# GPU_USB_PWM_Fan_Controller.net
KiCad netlist of a schematic drawn in EasyEDA Pro
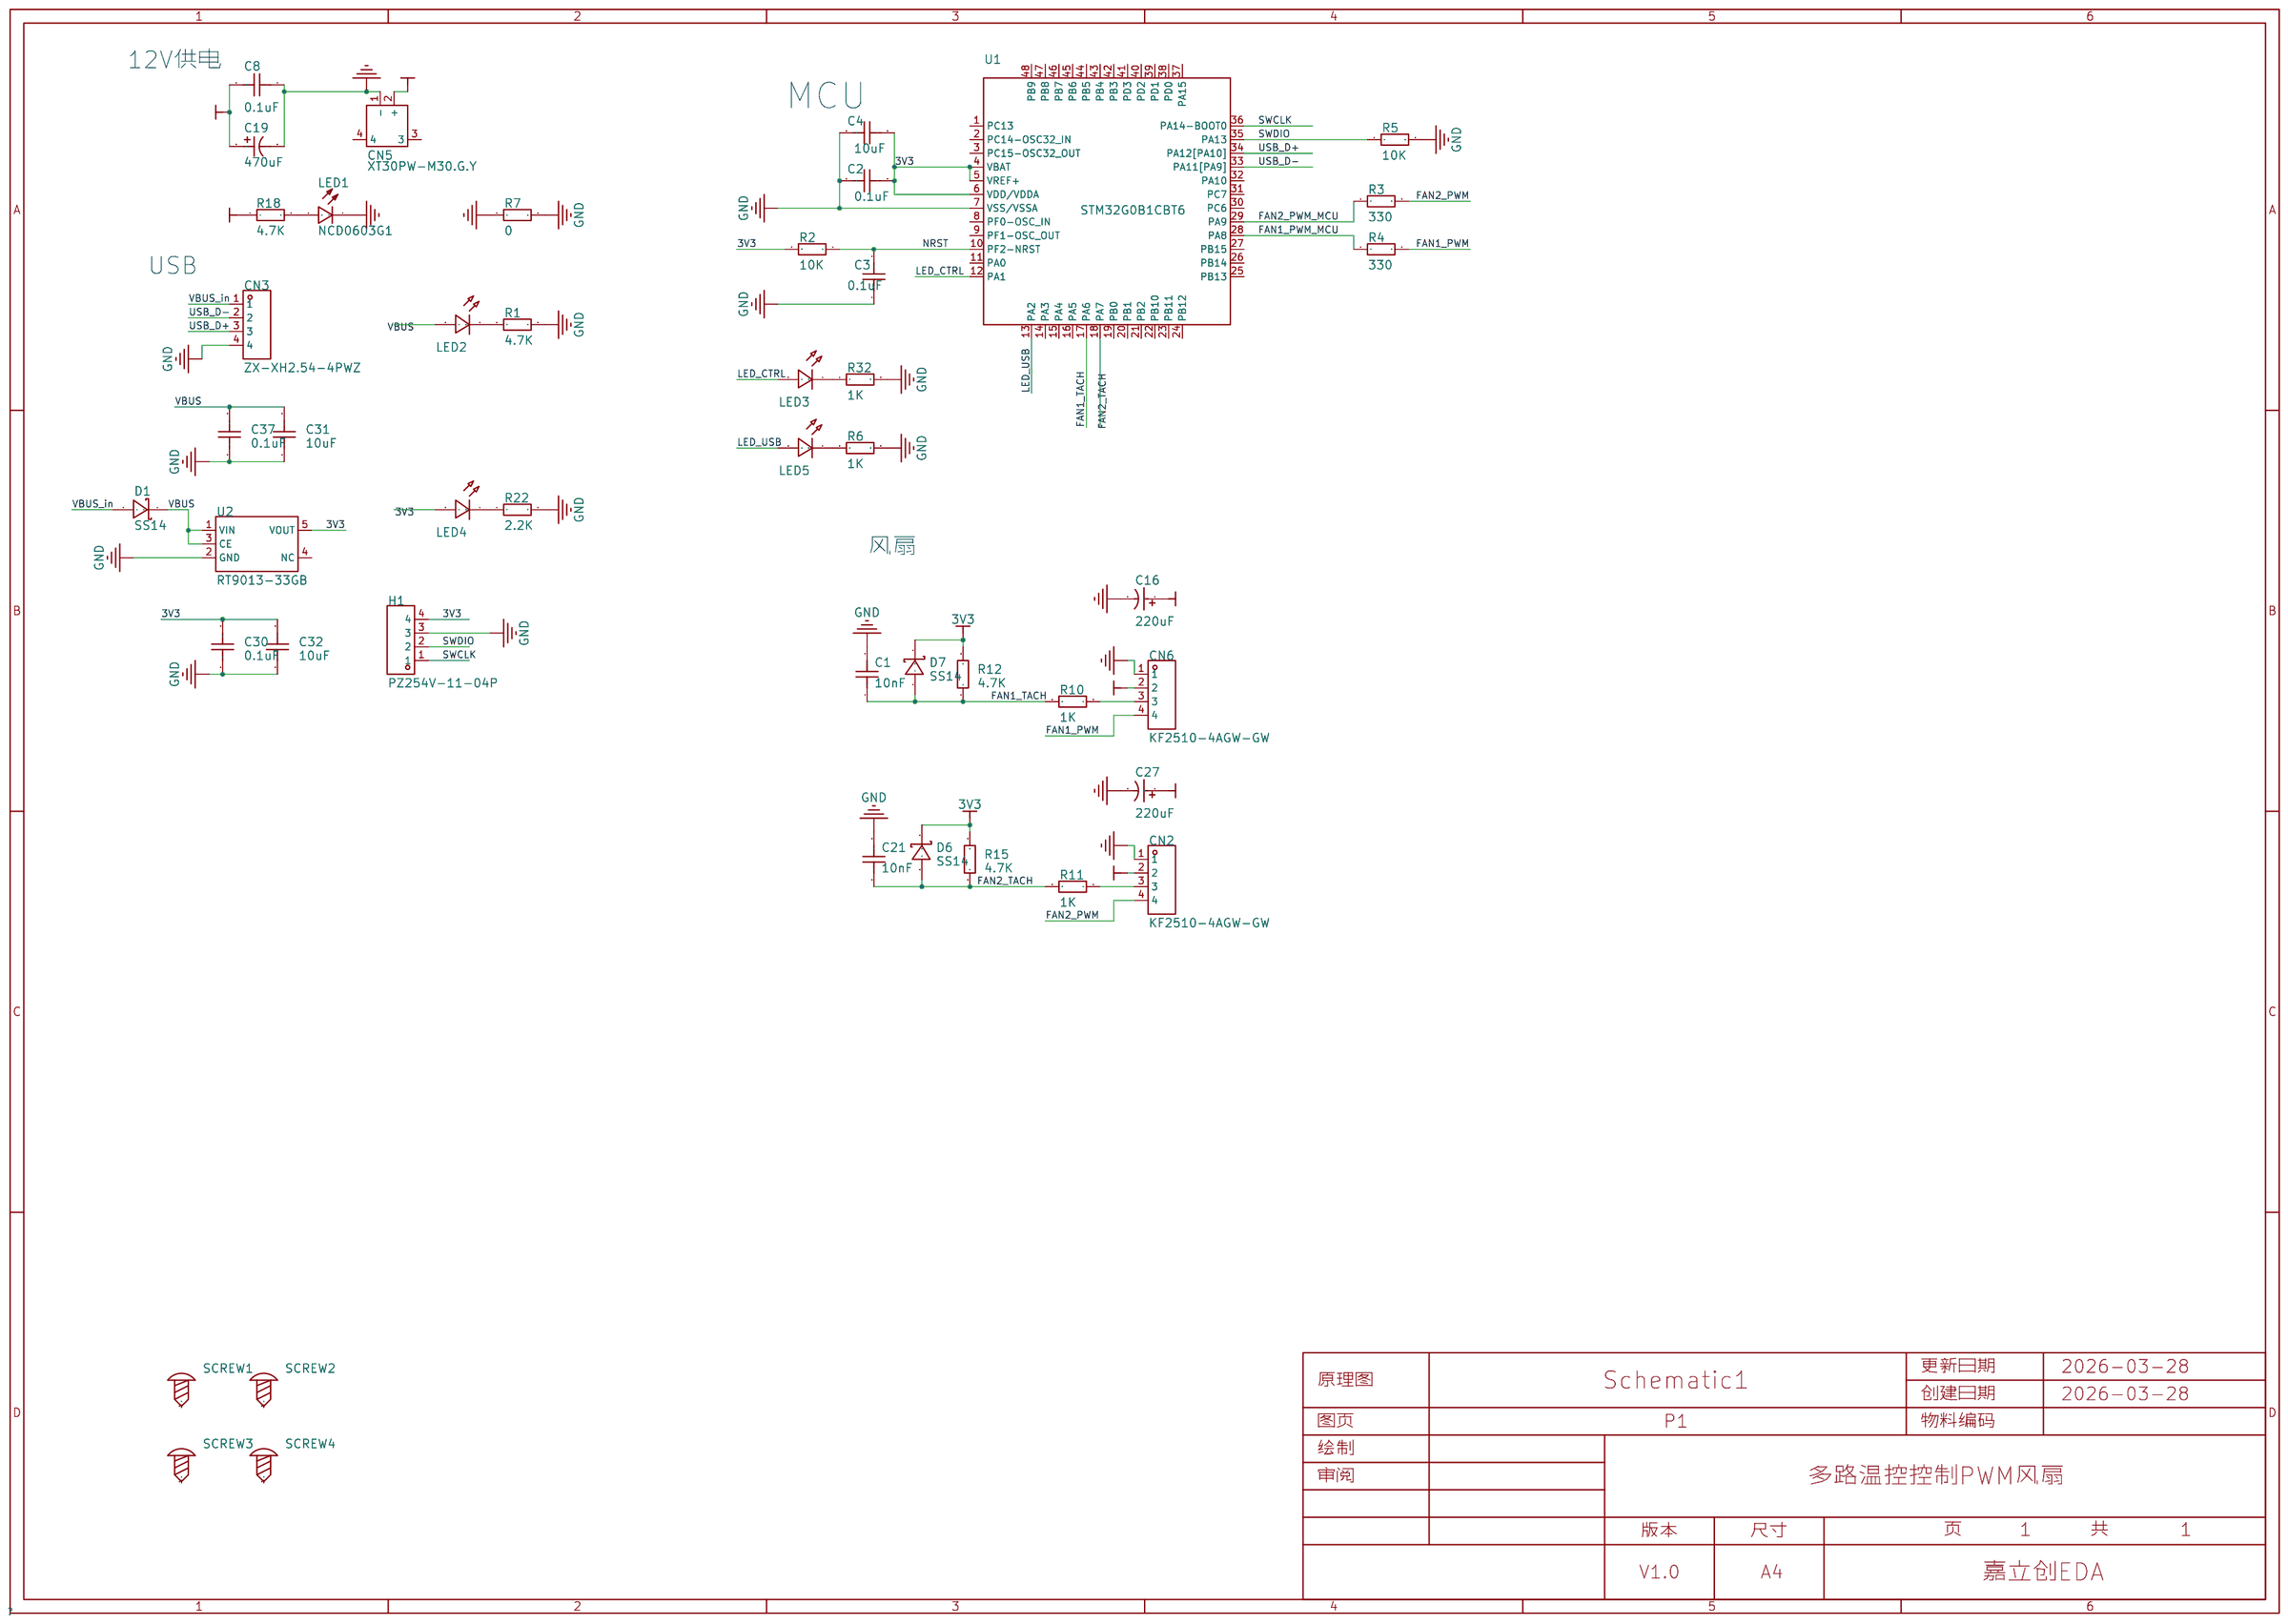
[diagram p0: schematic sheet]

(export (version "E")
  (design (tool "Eeschema 10.0.6"))
  (components
    (comp (ref "C1")
      (value "10nF")
      (footprint "easyedapro:C0603")
      (libsource (lib "easyedapro") (part "Capacitance"))
    )
    (comp (ref "C2")
      (value "0.1uF")
      (footprint "easyedapro:C0603")
      (libsource (lib "easyedapro") (part "Capacitance"))
    )
    (comp (ref "C3")
      (value "0.1uF")
      (footprint "easyedapro:C0603")
      (libsource (lib "easyedapro") (part "Capacitance"))
    )
    (comp (ref "C4")
      (value "10uF")
      (footprint "easyedapro:C0603")
      (libsource (lib "easyedapro") (part "Capacitance"))
    )
    (comp (ref "C8")
      (value "0.1uF")
      (footprint "easyedapro:C0603")
      (libsource (lib "easyedapro") (part "Capacitance"))
    )
    (comp (ref "C16")
      (value "220uF")
      (footprint "easyedapro:CAP-SMD_BD6.3-L6.6-W6.6-FD")
      (fields (field (name "Manufacturer Part") "RVT1A221M0605") (field (name "Manufacturer") "ROQANG(容强)"))
      (libsource (lib "easyedapro") (part "RVT1A221M0605-C72494"))
    )
    (comp (ref "C19")
      (value "470uF")
      (footprint "easyedapro:CAP-SMD_BD6.3-L6.6-W6.6-LS7.6-FD")
      (fields
        (field (name "Manufacturer Part") "RVT470UF10V67RV0159")
        (field (name "Manufacturer") "KNSCHA(科尼盛)")
      )
      (libsource (lib "easyedapro") (part "RVT470UF10V67RV0159"))
    )
    (comp (ref "C21")
      (value "10nF")
      (footprint "easyedapro:C0603")
      (libsource (lib "easyedapro") (part "Capacitance"))
    )
    (comp (ref "C27")
      (value "220uF")
      (footprint "easyedapro:CAP-SMD_BD6.3-L6.6-W6.6-FD")
      (fields (field (name "Manufacturer Part") "RVT1A221M0605") (field (name "Manufacturer") "ROQANG(容强)"))
      (libsource (lib "easyedapro") (part "RVT1A221M0605-C72494"))
    )
    (comp (ref "C30")
      (value "0.1uF")
      (footprint "easyedapro:C0603")
      (libsource (lib "easyedapro") (part "Capacitance"))
    )
    (comp (ref "C31")
      (value "10uF")
      (footprint "easyedapro:C0603")
      (libsource (lib "easyedapro") (part "Capacitance"))
    )
    (comp (ref "C32")
      (value "10uF")
      (footprint "easyedapro:C0603")
      (libsource (lib "easyedapro") (part "Capacitance"))
    )
    (comp (ref "C37")
      (value "0.1uF")
      (footprint "easyedapro:C0603")
      (libsource (lib "easyedapro") (part "Capacitance"))
    )
    (comp (ref "CN2")
      (value "KF2510-4AGW-GW")
      (footprint "easyedapro:CONN-TH_4P-P2.54_CAX_KF2510-4AGW-GW")
      (description "插针结构:1x4P;间距:2.54mm;安装方式:弯插;参考系列:-;总PIN数:4P;排数:1;每排PIN数:4;行距:-;额定电流:3A;触头材质:黄铜;工作温度:-25℃~+85℃;")
      (fields (field (name "Manufacturer") "CAX(创都)"))
      (libsource (lib "easyedapro") (part "KF2510-4AGW-GW"))
    )
    (comp (ref "CN3")
      (value "ZX-XH2.54-4PWZ")
      (footprint "easyedapro:CONN-TH_4P-P2.50_ZX-XH2.54-4PWZ")
      (fields (field (name "Manufacturer") "Megastar(兆星)"))
      (libsource (lib "easyedapro") (part "ZX-XH2.54-4PWZ"))
    )
    (comp (ref "CN5")
      (value "XT30PW-M30.G.Y")
      (footprint "easyedapro:CONN-TH_XT30PW-M")
      (fields (field (name "Manufacturer") "AMASS(艾迈斯)"))
      (libsource (lib "easyedapro") (part "XT30PW-M"))
    )
    (comp (ref "CN6")
      (value "KF2510-4AGW-GW")
      (footprint "easyedapro:CONN-TH_4P-P2.54_CAX_KF2510-4AGW-GW")
      (description "插针结构:1x4P;间距:2.54mm;安装方式:弯插;参考系列:-;总PIN数:4P;排数:1;每排PIN数:4;行距:-;额定电流:3A;触头材质:黄铜;工作温度:-25℃~+85℃;")
      (fields (field (name "Manufacturer") "CAX(创都)"))
      (libsource (lib "easyedapro") (part "KF2510-4AGW-GW"))
    )
    (comp (ref "D1")
      (value "SS14")
      (footprint "easyedapro:SMA_L4.3-W2.6-LS5.2-RD")
      (description "正向压降(Vf):500mV@1A;直流反向耐压(Vr):40V;整流电流:1A;")
      (fields (field (name "Manufacturer") "onsemi(安森美)"))
      (libsource (lib "easyedapro") (part "SS14_C83852"))
    )
    (comp (ref "D6")
      (value "SS14")
      (footprint "easyedapro:SMA_L4.3-W2.6-LS5.2-RD")
      (fields (field (name "Manufacturer") "onsemi(安森美)"))
      (libsource (lib "easyedapro") (part "SS14_C83852"))
    )
    (comp (ref "D7")
      (value "SS14")
      (footprint "easyedapro:SMA_L4.3-W2.6-LS5.2-RD")
      (fields (field (name "Manufacturer") "onsemi(安森美)"))
      (libsource (lib "easyedapro") (part "SS14_C83852"))
    )
    (comp (ref "H1")
      (value "PZ254V-11-04P")
      (footprint "easyedapro:HDR-TH_4P-P2.54-V-M")
      (fields (field (name "Manufacturer") "XFCN(兴飞)"))
      (libsource (lib "easyedapro") (part "PZ254V-11-04P_C2691448"))
    )
    (comp (ref "LED1")
      (value "NCD0603G1")
      (footprint "easyedapro:LED0603-RD_1")
      (fields (field (name "Manufacturer") "国星光电"))
      (libsource (lib "easyedapro") (part "FC-D1608UGK-520D10"))
    )
    (comp (ref "LED2")
      (value "~")
      (footprint "easyedapro:LED_0603")
      (libsource (lib "easyedapro") (part "LED_R"))
    )
    (comp (ref "LED3")
      (value "~")
      (footprint "easyedapro:LED_0603")
      (libsource (lib "easyedapro") (part "LED_R"))
    )
    (comp (ref "LED4")
      (value "~")
      (footprint "easyedapro:LED_0603")
      (libsource (lib "easyedapro") (part "LED_R"))
    )
    (comp (ref "LED5")
      (value "~")
      (footprint "easyedapro:LED_0603")
      (libsource (lib "easyedapro") (part "LED_R"))
    )
    (comp (ref "R1") (value "4.7K") (footprint "easyedapro:R0603") (libsource (lib "easyedapro") (part "电阻")))
    (comp (ref "R2") (value "10K") (footprint "easyedapro:R0603") (libsource (lib "easyedapro") (part "电阻")))
    (comp (ref "R3") (value "330") (footprint "easyedapro:R0603") (libsource (lib "easyedapro") (part "电阻")))
    (comp (ref "R4") (value "330") (footprint "easyedapro:R0603") (libsource (lib "easyedapro") (part "电阻")))
    (comp (ref "R5") (value "10K") (footprint "easyedapro:R0603") (libsource (lib "easyedapro") (part "电阻")))
    (comp (ref "R6") (value "1K") (footprint "easyedapro:R0603") (libsource (lib "easyedapro") (part "电阻")))
    (comp (ref "R7") (value "0") (footprint "easyedapro:R0603") (libsource (lib "easyedapro") (part "电阻")))
    (comp (ref "R10") (value "1K") (footprint "easyedapro:R0603") (libsource (lib "easyedapro") (part "电阻")))
    (comp (ref "R11") (value "1K") (footprint "easyedapro:R0603") (libsource (lib "easyedapro") (part "电阻")))
    (comp (ref "R12")
      (value "4.7K")
      (footprint "easyedapro:R0603")
      (libsource (lib "easyedapro") (part "电阻"))
    )
    (comp (ref "R15")
      (value "4.7K")
      (footprint "easyedapro:R0603")
      (libsource (lib "easyedapro") (part "电阻"))
    )
    (comp (ref "R18")
      (value "4.7K")
      (footprint "easyedapro:R0603")
      (libsource (lib "easyedapro") (part "电阻"))
    )
    (comp (ref "R22")
      (value "2.2K")
      (footprint "easyedapro:R0603")
      (libsource (lib "easyedapro") (part "电阻"))
    )
    (comp (ref "R32") (value "1K") (footprint "easyedapro:R0603") (libsource (lib "easyedapro") (part "电阻")))
    (comp (ref "SCREW1")
      (value "~")
      (footprint "easyedapro:M3螺丝")
      (libsource (lib "easyedapro") (part "螺丝孔"))
    )
    (comp (ref "SCREW2")
      (value "~")
      (footprint "easyedapro:M3螺丝")
      (libsource (lib "easyedapro") (part "螺丝孔"))
    )
    (comp (ref "SCREW3")
      (value "~")
      (footprint "easyedapro:M3螺丝")
      (libsource (lib "easyedapro") (part "螺丝孔"))
    )
    (comp (ref "SCREW4")
      (value "~")
      (footprint "easyedapro:M3螺丝")
      (libsource (lib "easyedapro") (part "螺丝孔"))
    )
    (comp (ref "U1")
      (value "STM32G0B1CBT6")
      (footprint "easyedapro:LQFP-48_L7.0-W7.0-P0.50-LS9.0-BL")
      (fields (field (name "Manufacturer") "ST(意法半导体)"))
      (libsource (lib "easyedapro") (part "STM32G0B1CBT6"))
    )
    (comp (ref "U2")
      (value "RT9013-33GB")
      (footprint "easyedapro:SOT-23-5_L2.9-W1.6-P0.95-LS2.8-BR")
      (fields (field (name "Manufacturer") "TECH PUBLIC(台舟)"))
      (libsource (lib "easyedapro") (part "RT9013-33GB_C19268157"))
    )
  )
  (nets
    (net (code "1") (name "/FAN1_PWM") (class "Default")
      (node (ref "CN6") (pin "4") (pinfunction "4_4") (pintype "unspecified"))
      (node (ref "R4") (pin "2") (pinfunction "2_2") (pintype "input"))
    )
    (net (code "2") (name "/FAN1_PWM_MCU") (class "Default")
      (node (ref "R4") (pin "1") (pinfunction "1_1") (pintype "input"))
      (node (ref "U1") (pin "28") (pinfunction "PA8_28") (pintype "unspecified"))
    )
    (net (code "3") (name "/FAN1_TACH") (class "Default")
      (node (ref "C1") (pin "1") (pinfunction "1_1") (pintype "input"))
      (node (ref "D7") (pin "2") (pinfunction "A_2") (pintype "unspecified"))
      (node (ref "R10") (pin "2") (pinfunction "2_2") (pintype "input"))
      (node (ref "R12") (pin "1") (pinfunction "1_1") (pintype "input"))
      (node (ref "U1") (pin "17") (pinfunction "PA6_17") (pintype "unspecified"))
    )
    (net (code "4") (name "/FAN2_PWM") (class "Default")
      (node (ref "CN2") (pin "4") (pinfunction "4_4") (pintype "unspecified"))
      (node (ref "R3") (pin "2") (pinfunction "2_2") (pintype "input"))
    )
    (net (code "5") (name "/FAN2_PWM_MCU") (class "Default")
      (node (ref "R3") (pin "1") (pinfunction "1_1") (pintype "input"))
      (node (ref "U1") (pin "29") (pinfunction "PA9_29") (pintype "unspecified"))
    )
    (net (code "6") (name "/FAN2_TACH") (class "Default")
      (node (ref "C21") (pin "1") (pinfunction "1_1") (pintype "input"))
      (node (ref "D6") (pin "2") (pinfunction "A_2") (pintype "unspecified"))
      (node (ref "R11") (pin "2") (pinfunction "2_2") (pintype "input"))
      (node (ref "R15") (pin "1") (pinfunction "1_1") (pintype "input"))
      (node (ref "U1") (pin "18") (pinfunction "PA7_18") (pintype "unspecified"))
    )
    (net (code "7") (name "/LED_CTRL") (class "Default")
      (node (ref "LED3") (pin "2") (pinfunction "A_2") (pintype "input"))
      (node (ref "U1") (pin "12") (pinfunction "PA1_12") (pintype "unspecified"))
    )
    (net (code "8") (name "/LED_USB") (class "Default")
      (node (ref "LED5") (pin "2") (pinfunction "A_2") (pintype "input"))
      (node (ref "U1") (pin "13") (pinfunction "PA2_13") (pintype "unspecified"))
    )
    (net (code "9") (name "/NRST") (class "Default")
      (node (ref "C3") (pin "2") (pinfunction "2_2") (pintype "input"))
      (node (ref "R2") (pin "1") (pinfunction "1_1") (pintype "input"))
      (node (ref "U1") (pin "10") (pinfunction "PF2-NRST_10") (pintype "unspecified"))
    )
    (net (code "10") (name "/SWCLK") (class "Default")
      (node (ref "H1") (pin "1") (pinfunction "1_1") (pintype "unspecified"))
      (node (ref "U1") (pin "36") (pinfunction "PA14-BOOT0_36") (pintype "unspecified"))
    )
    (net (code "11") (name "/SWDIO") (class "Default")
      (node (ref "H1") (pin "2") (pinfunction "2_2") (pintype "unspecified"))
      (node (ref "R5") (pin "1") (pinfunction "1_1") (pintype "input"))
      (node (ref "U1") (pin "35") (pinfunction "PA13_35") (pintype "unspecified"))
    )
    (net (code "12") (name "/USB_D+") (class "Default")
      (node (ref "CN3") (pin "3") (pinfunction "3_3") (pintype "unspecified"))
      (node (ref "U1") (pin "34") (pinfunction "PA12[PA10]_34") (pintype "unspecified"))
    )
    (net (code "13") (name "/USB_D-") (class "Default")
      (node (ref "CN3") (pin "2") (pinfunction "2_2") (pintype "unspecified"))
      (node (ref "U1") (pin "33") (pinfunction "PA11[PA9]_33") (pintype "unspecified"))
    )
    (net (code "14") (name "/VBUS") (class "Default")
      (node (ref "C31") (pin "2") (pinfunction "2_2") (pintype "input"))
      (node (ref "C37") (pin "2") (pinfunction "2_2") (pintype "input"))
      (node (ref "D1") (pin "1") (pinfunction "K_1") (pintype "unspecified"))
      (node (ref "LED2") (pin "2") (pinfunction "A_2") (pintype "input"))
      (node (ref "U2") (pin "1") (pinfunction "VIN_1") (pintype "unspecified"))
      (node (ref "U2") (pin "3") (pinfunction "CE_3") (pintype "unspecified"))
    )
    (net (code "15") (name "/VBUS_in") (class "Default")
      (node (ref "CN3") (pin "1") (pinfunction "1_1") (pintype "unspecified"))
      (node (ref "D1") (pin "2") (pinfunction "A_2") (pintype "unspecified"))
    )
    (net (code "16") (name "3V3") (class "Default")
      (node (ref "C2") (pin "1") (pinfunction "1_1") (pintype "input"))
      (node (ref "C30") (pin "2") (pinfunction "2_2") (pintype "input"))
      (node (ref "C32") (pin "2") (pinfunction "2_2") (pintype "input"))
      (node (ref "C4") (pin "1") (pinfunction "1_1") (pintype "input"))
      (node (ref "D6") (pin "1") (pinfunction "K_1") (pintype "unspecified"))
      (node (ref "D7") (pin "1") (pinfunction "K_1") (pintype "unspecified"))
      (node (ref "H1") (pin "4") (pinfunction "4_4") (pintype "unspecified"))
      (node (ref "LED4") (pin "2") (pinfunction "A_2") (pintype "input"))
      (node (ref "R12") (pin "2") (pinfunction "2_2") (pintype "input"))
      (node (ref "R15") (pin "2") (pinfunction "2_2") (pintype "input"))
      (node (ref "R2") (pin "2") (pinfunction "2_2") (pintype "input"))
      (node (ref "U1") (pin "4") (pinfunction "VBAT_4") (pintype "unspecified"))
      (node (ref "U1") (pin "5") (pinfunction "VREF+_5") (pintype "unspecified"))
      (node (ref "U1") (pin "6") (pinfunction "VDD/VDDA_6") (pintype "unspecified"))
      (node (ref "U2") (pin "5") (pinfunction "VOUT_5") (pintype "unspecified"))
    )
    (net (code "17") (name "12V") (class "Default")
      (node (ref "C16") (pin "1") (pinfunction "1_1") (pintype "input"))
      (node (ref "C19") (pin "1") (pinfunction "1_1") (pintype "input"))
      (node (ref "C27") (pin "1") (pinfunction "1_1") (pintype "input"))
      (node (ref "C8") (pin "2") (pinfunction "2_2") (pintype "input"))
      (node (ref "CN2") (pin "2") (pinfunction "2_2") (pintype "unspecified"))
      (node (ref "CN5") (pin "2") (pinfunction "+_2") (pintype "unspecified"))
      (node (ref "CN6") (pin "2") (pinfunction "2_2") (pintype "unspecified"))
      (node (ref "R18") (pin "1") (pinfunction "1_1") (pintype "input"))
    )
    (net (code "18") (name "GND") (class "Default")
      (node (ref "C1") (pin "2") (pinfunction "2_2") (pintype "input"))
      (node (ref "C2") (pin "2") (pinfunction "2_2") (pintype "input"))
      (node (ref "C21") (pin "2") (pinfunction "2_2") (pintype "input"))
      (node (ref "C3") (pin "1") (pinfunction "1_1") (pintype "input"))
      (node (ref "C30") (pin "1") (pinfunction "1_1") (pintype "input"))
      (node (ref "C31") (pin "1") (pinfunction "1_1") (pintype "input"))
      (node (ref "C32") (pin "1") (pinfunction "1_1") (pintype "input"))
      (node (ref "C37") (pin "1") (pinfunction "1_1") (pintype "input"))
      (node (ref "C4") (pin "2") (pinfunction "2_2") (pintype "input"))
      (node (ref "CN3") (pin "4") (pinfunction "4_4") (pintype "unspecified"))
      (node (ref "H1") (pin "3") (pinfunction "3_3") (pintype "unspecified"))
      (node (ref "R1") (pin "2") (pinfunction "2_2") (pintype "input"))
      (node (ref "R22") (pin "2") (pinfunction "2_2") (pintype "input"))
      (node (ref "R32") (pin "2") (pinfunction "2_2") (pintype "input"))
      (node (ref "R5") (pin "2") (pinfunction "2_2") (pintype "input"))
      (node (ref "R6") (pin "2") (pinfunction "2_2") (pintype "input"))
      (node (ref "R7") (pin "2") (pinfunction "2_2") (pintype "input"))
      (node (ref "U1") (pin "7") (pinfunction "VSS/VSSA_7") (pintype "unspecified"))
      (node (ref "U2") (pin "2") (pinfunction "GND_2") (pintype "unspecified"))
    )
    (net (code "19") (name "Net-(CN2-Pad3)") (class "Default")
      (node (ref "CN2") (pin "3") (pinfunction "3_3") (pintype "unspecified"))
      (node (ref "R11") (pin "1") (pinfunction "1_1") (pintype "input"))
    )
    (net (code "20") (name "Net-(CN6-Pad3)") (class "Default")
      (node (ref "CN6") (pin "3") (pinfunction "3_3") (pintype "unspecified"))
      (node (ref "R10") (pin "1") (pinfunction "1_1") (pintype "input"))
    )
    (net (code "21") (name "Net-(LED1-A)") (class "Default")
      (node (ref "LED1") (pin "2") (pinfunction "A_2") (pintype "input"))
      (node (ref "R18") (pin "2") (pinfunction "2_2") (pintype "input"))
    )
    (net (code "22") (name "Net-(LED2-C)") (class "Default")
      (node (ref "LED2") (pin "1") (pinfunction "C_1") (pintype "input"))
      (node (ref "R1") (pin "1") (pinfunction "1_1") (pintype "input"))
    )
    (net (code "23") (name "Net-(LED3-C)") (class "Default")
      (node (ref "LED3") (pin "1") (pinfunction "C_1") (pintype "input"))
      (node (ref "R32") (pin "1") (pinfunction "1_1") (pintype "input"))
    )
    (net (code "24") (name "Net-(LED4-C)") (class "Default")
      (node (ref "LED4") (pin "1") (pinfunction "C_1") (pintype "input"))
      (node (ref "R22") (pin "1") (pinfunction "1_1") (pintype "input"))
    )
    (net (code "25") (name "Net-(LED5-C)") (class "Default")
      (node (ref "LED5") (pin "1") (pinfunction "C_1") (pintype "input"))
      (node (ref "R6") (pin "1") (pinfunction "1_1") (pintype "input"))
    )
    (net (code "26") (name "PGND") (class "Default")
      (node (ref "C16") (pin "2") (pinfunction "2_2") (pintype "input"))
      (node (ref "C19") (pin "2") (pinfunction "2_2") (pintype "input"))
      (node (ref "C27") (pin "2") (pinfunction "2_2") (pintype "input"))
      (node (ref "C8") (pin "1") (pinfunction "1_1") (pintype "input"))
      (node (ref "CN2") (pin "1") (pinfunction "1_1") (pintype "unspecified"))
      (node (ref "CN5") (pin "1") (pinfunction "-_1") (pintype "unspecified"))
      (node (ref "CN6") (pin "1") (pinfunction "1_1") (pintype "unspecified"))
      (node (ref "LED1") (pin "1") (pinfunction "K_1") (pintype "input"))
      (node (ref "R7") (pin "1") (pinfunction "1_1") (pintype "input"))
    )
    (net (code "27") (name "unconnected-(CN5-Pad3)") (class "Default")
      (node (ref "CN5") (pin "3") (pinfunction "3_3") (pintype "unspecified"))
    )
    (net (code "28") (name "unconnected-(CN5-Pad4)") (class "Default")
      (node (ref "CN5") (pin "4") (pinfunction "4_4") (pintype "unspecified"))
    )
    (net (code "29") (name "unconnected-(SCREW1-Pad1)") (class "Default")
      (node (ref "SCREW1") (pin "1") (pinfunction "1_1") (pintype "input"))
    )
    (net (code "30") (name "unconnected-(SCREW2-Pad1)") (class "Default")
      (node (ref "SCREW2") (pin "1") (pinfunction "1_1") (pintype "input"))
    )
    (net (code "31") (name "unconnected-(SCREW3-Pad1)") (class "Default")
      (node (ref "SCREW3") (pin "1") (pinfunction "1_1") (pintype "input"))
    )
    (net (code "32") (name "unconnected-(SCREW4-Pad1)") (class "Default")
      (node (ref "SCREW4") (pin "1") (pinfunction "1_1") (pintype "input"))
    )
    (net (code "33") (name "unconnected-(U1-PA0-Pad11)") (class "Default")
      (node (ref "U1") (pin "11") (pinfunction "PA0_11") (pintype "unspecified"))
    )
    (net (code "34") (name "unconnected-(U1-PA3-Pad14)") (class "Default")
      (node (ref "U1") (pin "14") (pinfunction "PA3_14") (pintype "unspecified"))
    )
    (net (code "35") (name "unconnected-(U1-PA4-Pad15)") (class "Default")
      (node (ref "U1") (pin "15") (pinfunction "PA4_15") (pintype "unspecified"))
    )
    (net (code "36") (name "unconnected-(U1-PA5-Pad16)") (class "Default")
      (node (ref "U1") (pin "16") (pinfunction "PA5_16") (pintype "unspecified"))
    )
    (net (code "37") (name "unconnected-(U1-PA10-Pad32)") (class "Default")
      (node (ref "U1") (pin "32") (pinfunction "PA10_32") (pintype "unspecified"))
    )
    (net (code "38") (name "unconnected-(U1-PA15-Pad37)") (class "Default")
      (node (ref "U1") (pin "37") (pinfunction "PA15_37") (pintype "unspecified"))
    )
    (net (code "39") (name "unconnected-(U1-PB0-Pad19)") (class "Default")
      (node (ref "U1") (pin "19") (pinfunction "PB0_19") (pintype "unspecified"))
    )
    (net (code "40") (name "unconnected-(U1-PB1-Pad20)") (class "Default")
      (node (ref "U1") (pin "20") (pinfunction "PB1_20") (pintype "unspecified"))
    )
    (net (code "41") (name "unconnected-(U1-PB2-Pad21)") (class "Default")
      (node (ref "U1") (pin "21") (pinfunction "PB2_21") (pintype "unspecified"))
    )
    (net (code "42") (name "unconnected-(U1-PB3-Pad42)") (class "Default")
      (node (ref "U1") (pin "42") (pinfunction "PB3_42") (pintype "unspecified"))
    )
    (net (code "43") (name "unconnected-(U1-PB4-Pad43)") (class "Default")
      (node (ref "U1") (pin "43") (pinfunction "PB4_43") (pintype "unspecified"))
    )
    (net (code "44") (name "unconnected-(U1-PB5-Pad44)") (class "Default")
      (node (ref "U1") (pin "44") (pinfunction "PB5_44") (pintype "unspecified"))
    )
    (net (code "45") (name "unconnected-(U1-PB6-Pad45)") (class "Default")
      (node (ref "U1") (pin "45") (pinfunction "PB6_45") (pintype "unspecified"))
    )
    (net (code "46") (name "unconnected-(U1-PB7-Pad46)") (class "Default")
      (node (ref "U1") (pin "46") (pinfunction "PB7_46") (pintype "unspecified"))
    )
    (net (code "47") (name "unconnected-(U1-PB8-Pad47)") (class "Default")
      (node (ref "U1") (pin "47") (pinfunction "PB8_47") (pintype "unspecified"))
    )
    (net (code "48") (name "unconnected-(U1-PB9-Pad48)") (class "Default")
      (node (ref "U1") (pin "48") (pinfunction "PB9_48") (pintype "unspecified"))
    )
    (net (code "49") (name "unconnected-(U1-PB10-Pad22)") (class "Default")
      (node (ref "U1") (pin "22") (pinfunction "PB10_22") (pintype "unspecified"))
    )
    (net (code "50") (name "unconnected-(U1-PB11-Pad23)") (class "Default")
      (node (ref "U1") (pin "23") (pinfunction "PB11_23") (pintype "unspecified"))
    )
    (net (code "51") (name "unconnected-(U1-PB12-Pad24)") (class "Default")
      (node (ref "U1") (pin "24") (pinfunction "PB12_24") (pintype "unspecified"))
    )
    (net (code "52") (name "unconnected-(U1-PB13-Pad25)") (class "Default")
      (node (ref "U1") (pin "25") (pinfunction "PB13_25") (pintype "unspecified"))
    )
    (net (code "53") (name "unconnected-(U1-PB14-Pad26)") (class "Default")
      (node (ref "U1") (pin "26") (pinfunction "PB14_26") (pintype "unspecified"))
    )
    (net (code "54") (name "unconnected-(U1-PB15-Pad27)") (class "Default")
      (node (ref "U1") (pin "27") (pinfunction "PB15_27") (pintype "unspecified"))
    )
    (net (code "55") (name "unconnected-(U1-PC6-Pad30)") (class "Default")
      (node (ref "U1") (pin "30") (pinfunction "PC6_30") (pintype "unspecified"))
    )
    (net (code "56") (name "unconnected-(U1-PC7-Pad31)") (class "Default")
      (node (ref "U1") (pin "31") (pinfunction "PC7_31") (pintype "unspecified"))
    )
    (net (code "57") (name "unconnected-(U1-PC13-Pad1)") (class "Default")
      (node (ref "U1") (pin "1") (pinfunction "PC13_1") (pintype "unspecified"))
    )
    (net (code "58") (name "unconnected-(U1-PC14-OSC32_IN-Pad2)") (class "Default")
      (node (ref "U1") (pin "2") (pinfunction "PC14-OSC32_IN_2") (pintype "unspecified"))
    )
    (net (code "59") (name "unconnected-(U1-PC15-OSC32_OUT-Pad3)") (class "Default")
      (node (ref "U1") (pin "3") (pinfunction "PC15-OSC32_OUT_3") (pintype "unspecified"))
    )
    (net (code "60") (name "unconnected-(U1-PD0-Pad38)") (class "Default")
      (node (ref "U1") (pin "38") (pinfunction "PD0_38") (pintype "unspecified"))
    )
    (net (code "61") (name "unconnected-(U1-PD1-Pad39)") (class "Default")
      (node (ref "U1") (pin "39") (pinfunction "PD1_39") (pintype "unspecified"))
    )
    (net (code "62") (name "unconnected-(U1-PD2-Pad40)") (class "Default")
      (node (ref "U1") (pin "40") (pinfunction "PD2_40") (pintype "unspecified"))
    )
    (net (code "63") (name "unconnected-(U1-PD3-Pad41)") (class "Default")
      (node (ref "U1") (pin "41") (pinfunction "PD3_41") (pintype "unspecified"))
    )
    (net (code "64") (name "unconnected-(U1-PF0-OSC_IN-Pad8)") (class "Default")
      (node (ref "U1") (pin "8") (pinfunction "PF0-OSC_IN_8") (pintype "unspecified"))
    )
    (net (code "65") (name "unconnected-(U1-PF1-OSC_OUT-Pad9)") (class "Default")
      (node (ref "U1") (pin "9") (pinfunction "PF1-OSC_OUT_9") (pintype "unspecified"))
    )
    (net (code "66") (name "unconnected-(U2-NC-Pad4)") (class "Default")
      (node (ref "U2") (pin "4") (pinfunction "NC_4") (pintype "unspecified"))
    )
  )
)
